# esp8285-programmer-v1_0.net
KiCad netlist of a schematic drawn in EAGLE
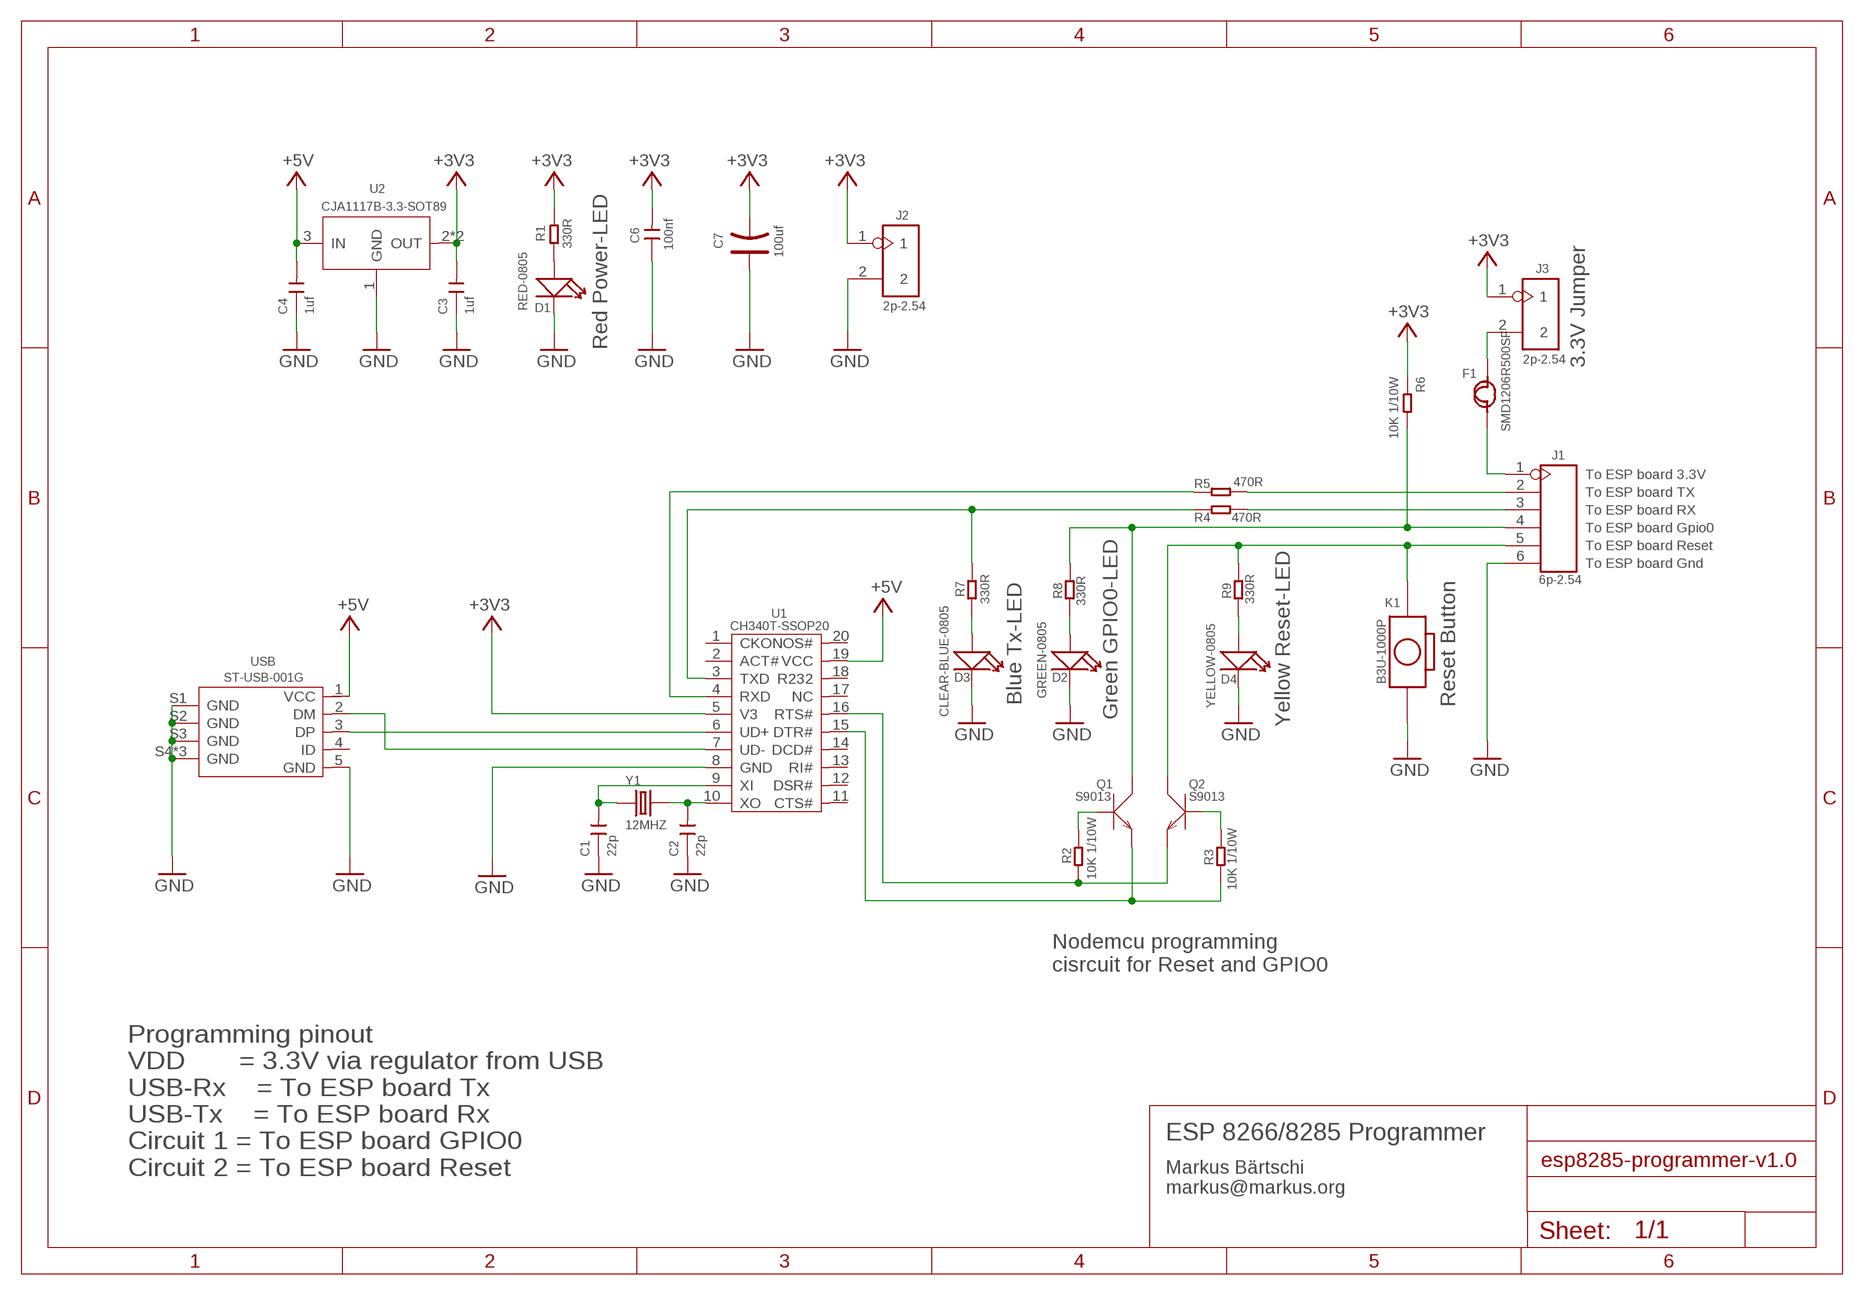
[diagram p0: schematic, sheet 1]

(export (version "E")
  (design (tool "Eeschema 10.0.6"))
  (components
    (comp (ref "C1")
      (value "22p")
      (footprint "eagle-import:C0603")
      (libsource (lib "eagle-import") (part "CERAMIC-10PF-50V-5%-NPO(0603)"))
    )
    (comp (ref "C2")
      (value "22p")
      (footprint "eagle-import:C0603")
      (libsource (lib "eagle-import") (part "CERAMIC-10PF-50V-5%-NPO(0603)"))
    )
    (comp (ref "C3")
      (value "1uf")
      (footprint "eagle-import:C0603")
      (fields (field (name "MPN") "CC0603KRX7R8BB105"))
      (libsource (lib "eagle-import") (part "CERAMIC-1UF-25V-10%-X7R(0603)"))
    )
    (comp (ref "C4")
      (value "1uf")
      (footprint "eagle-import:C0603")
      (fields (field (name "MPN") "CC0603KRX7R8BB105"))
      (libsource (lib "eagle-import") (part "CERAMIC-1UF-25V-10%-X7R(0603)"))
    )
    (comp (ref "C6")
      (value "100nf")
      (footprint "eagle-import:C0603")
      (fields (field (name "MPN") "CC0603KRX7R9BB104"))
      (libsource (lib "eagle-import") (part "CERAMIC-100NF-50V-10%-X7R(0603)"))
    )
    (comp (ref "C7")
      (value "100uf")
      (footprint "eagle-import:AVX-B")
      (fields (field (name "MPN") "TAJB107M006RNJ"))
      (libsource (lib "eagle-import") (part "TANTALUM-SMD-100UF-6.3V(AVX-B)"))
    )
    (comp (ref "D1")
      (value "RED-0805")
      (footprint "eagle-import:LED-0805")
      (fields (field (name "MPN") "17-215SURC/S530-A2/TR8"))
      (libsource (lib "eagle-import") (part "SMD-LED-CLEAR-RED(0805)"))
    )
    (comp (ref "D2")
      (value "GREEN-0805")
      (footprint "eagle-import:LED-0805")
      (fields (field (name "MPN") "17-215SYGC/S530-E2/TR8"))
      (libsource (lib "eagle-import") (part "SMD-LED-CLEAR-GREEN(0805)"))
    )
    (comp (ref "D3")
      (value "CLEAR-BLUE-0805")
      (footprint "eagle-import:LED-0805")
      (fields (field (name "MPN") "EL-17-215/BHC-AN1P2/3T"))
      (libsource (lib "eagle-import") (part "SMD-LED-CLEAR-BLUE(0805)"))
    )
    (comp (ref "D4")
      (value "YELLOW-0805")
      (footprint "eagle-import:LED-0805")
      (fields (field (name "MPN") "17-215UYC/S530-A3/TR8"))
      (libsource (lib "eagle-import") (part "SMD-LED-CLEAR-YELLOW(0805)"))
    )
    (comp (ref "F1")
      (value "SMD1206R500SF")
      (footprint "eagle-import:F1206")
      (libsource (lib "eagle-import") (part "SMD-PPTC-500MA(1206)"))
    )
    (comp (ref "J1")
      (value "6p-2.54")
      (footprint "eagle-import:H6-2.54")
      (fields (field (name "MPN") "P125-1106A1BS116A1"))
      (libsource (lib "eagle-import") (part "DIP-BLACK-MALE-HEADER(6P-2.54)"))
    )
    (comp (ref "J2")
      (value "2p-2.54")
      (footprint "eagle-import:H2-2.54")
      (fields (field (name "MPN") "P125-1102A0BS116A1"))
      (libsource (lib "eagle-import") (part "DIP-BLACK-MALE-HEADER-VERT(2P-2.54)"))
    )
    (comp (ref "J3")
      (value "2p-2.54")
      (footprint "eagle-import:H2-2.54")
      (fields (field (name "MPN") "P125-1102A0BS116A1"))
      (libsource (lib "eagle-import") (part "DIP-BLACK-MALE-HEADER-VERT(2P-2.54)"))
    )
    (comp (ref "K1")
      (value "B3U-1000P")
      (footprint "eagle-import:SW2-SMD-3.0X2.5X1.2+0.4MM")
      (libsource (lib "eagle-import") (part "SMD-BUTTON-WITHOUT-BOSS-(2P-3X2.5MM)"))
    )
    (comp (ref "Q1")
      (value "S9013")
      (footprint "eagle-import:SOT-23")
      (libsource (lib "eagle-import") (part "SMD-TRANSISTORS-NPN-25V-500MA-S9013(SOT-23)"))
    )
    (comp (ref "Q2")
      (value "S9013")
      (footprint "eagle-import:SOT-23")
      (libsource (lib "eagle-import") (part "SMD-TRANSISTORS-NPN-25V-500MA-S9013(SOT-23)"))
    )
    (comp (ref "R1")
      (value "330R")
      (footprint "eagle-import:R0603")
      (fields (field (name "MPN") "RC0603FR-07330RL"))
      (libsource (lib "eagle-import") (part "SMD-RES-330R-1%-1/10W(0603)"))
    )
    (comp (ref "R2")
      (value "10K 1/10W")
      (footprint "eagle-import:R0603")
      (fields (field (name "MPN") "RC0603JR-0710KL"))
      (libsource (lib "eagle-import") (part "SMD-RES-10K-5%-1/10W(0603)"))
    )
    (comp (ref "R3")
      (value "10K 1/10W")
      (footprint "eagle-import:R0603")
      (fields (field (name "MPN") "RC0603JR-0710KL"))
      (libsource (lib "eagle-import") (part "SMD-RES-10K-5%-1/10W(0603)"))
    )
    (comp (ref "R4")
      (value "470R")
      (footprint "eagle-import:R0603")
      (fields (field (name "MPN") "RC0603JR-07470RL"))
      (libsource (lib "eagle-import") (part "SMD-RES-470R-5%-1/10W(0603)"))
    )
    (comp (ref "R5")
      (value "470R")
      (footprint "eagle-import:R0603")
      (fields (field (name "MPN") "RC0603JR-07470RL"))
      (libsource (lib "eagle-import") (part "SMD-RES-470R-5%-1/10W(0603)"))
    )
    (comp (ref "R6")
      (value "10K 1/10W")
      (footprint "eagle-import:R0603")
      (fields (field (name "MPN") "RC0603JR-0710KL"))
      (libsource (lib "eagle-import") (part "SMD-RES-10K-5%-1/10W(0603)"))
    )
    (comp (ref "R7")
      (value "330R")
      (footprint "eagle-import:R0603")
      (fields (field (name "MPN") "RC0603FR-07330RL"))
      (libsource (lib "eagle-import") (part "SMD-RES-330R-1%-1/10W(0603)"))
    )
    (comp (ref "R8")
      (value "330R")
      (footprint "eagle-import:R0603")
      (fields (field (name "MPN") "RC0603FR-07330RL"))
      (libsource (lib "eagle-import") (part "SMD-RES-330R-1%-1/10W(0603)"))
    )
    (comp (ref "R9")
      (value "330R")
      (footprint "eagle-import:R0603")
      (fields (field (name "MPN") "RC0603FR-07330RL"))
      (libsource (lib "eagle-import") (part "SMD-RES-330R-1%-1/10W(0603)"))
    )
    (comp (ref "U1")
      (value "CH340T-SSOP20")
      (footprint "eagle-import:SSOP20-0.65-7.6X5.2MM")
      (fields (field (name "MPN") "CH340T"))
      (libsource (lib "eagle-import") (part "INTERFACE-CH340T(SSOP20)"))
    )
    (comp (ref "U2")
      (value "CJA1117B-3.3-SOT89")
      (footprint "eagle-import:SOT-89")
      (fields (field (name "MPN") "CJA1117B-3.3"))
      (libsource (lib "eagle-import") (part "PMIC-CJA1117B-3.3(SOT-89)"))
    )
    (comp (ref "USB")
      (value "ST-USB-001G")
      (footprint "eagle-import:MICRO-USB5+4P-SMD-0.65-B")
      (libsource (lib "eagle-import") (part "MICRO-USB-SMD-B-WITHOUT-POST-W/P(ST-USB-001G)"))
    )
    (comp (ref "Y1")
      (value "12MHZ")
      (footprint "eagle-import:X2-SMD-5.0X3.2X1.3MM")
      (fields (field (name "MPN") "5032/2P"))
      (libsource (lib "eagle-import") (part "SMD-CRYSTAL-12MHZ-20PF-20PPM-40R(2P-5.0X3.2MM)"))
    )
  )
  (nets
    (net (code "1") (name "+3V3") (class "Default")
      (node (ref "C3") (pin "2") (pinfunction "2_2") (pintype "passive"))
      (node (ref "C6") (pin "2") (pinfunction "2_2") (pintype "passive"))
      (node (ref "C7") (pin "-") (pinfunction "-_-") (pintype "passive"))
      (node (ref "J2") (pin "1") (pinfunction "1_1") (pintype "bidirectional"))
      (node (ref "J3") (pin "1") (pinfunction "1_1") (pintype "bidirectional"))
      (node (ref "R1") (pin "2") (pinfunction "2_2") (pintype "passive"))
      (node (ref "R6") (pin "1") (pinfunction "1_1") (pintype "passive"))
      (node (ref "U1") (pin "5") (pinfunction "V3_5") (pintype "power_in"))
      (node (ref "U2") (pin "2") (pinfunction "OUT_2") (pintype "bidirectional"))
      (node (ref "U2") (pin "4") (pinfunction "OUT_4") (pintype "bidirectional"))
    )
    (net (code "2") (name "+5V") (class "Default")
      (node (ref "C4") (pin "2") (pinfunction "2_2") (pintype "passive"))
      (node (ref "U1") (pin "19") (pinfunction "VCC_19") (pintype "power_in"))
      (node (ref "U2") (pin "3") (pinfunction "IN_3") (pintype "bidirectional"))
      (node (ref "USB") (pin "1") (pinfunction "VCC_1") (pintype "bidirectional"))
    )
    (net (code "3") (name "/NOS#") (class "Default")
      (node (ref "U1") (pin "20") (pinfunction "NOS#_20") (pintype "power_in"))
    )
    (net (code "4") (name "GND") (class "Default")
      (node (ref "C1") (pin "1") (pinfunction "1_1") (pintype "passive"))
      (node (ref "C2") (pin "1") (pinfunction "1_1") (pintype "passive"))
      (node (ref "C3") (pin "1") (pinfunction "1_1") (pintype "passive"))
      (node (ref "C4") (pin "1") (pinfunction "1_1") (pintype "passive"))
      (node (ref "C6") (pin "1") (pinfunction "1_1") (pintype "passive"))
      (node (ref "C7") (pin "+") (pinfunction "+_+") (pintype "passive"))
      (node (ref "D1") (pin "-") (pinfunction "-_-") (pintype "passive"))
      (node (ref "D2") (pin "-") (pinfunction "-_-") (pintype "passive"))
      (node (ref "D3") (pin "-") (pinfunction "-_-") (pintype "passive"))
      (node (ref "D4") (pin "-") (pinfunction "-_-") (pintype "passive"))
      (node (ref "J1") (pin "6") (pinfunction "6_6") (pintype "bidirectional"))
      (node (ref "J2") (pin "2") (pinfunction "2_2") (pintype "bidirectional"))
      (node (ref "K1") (pin "1") (pinfunction "1_1") (pintype "bidirectional"))
      (node (ref "U1") (pin "8") (pinfunction "GND_8") (pintype "power_in"))
      (node (ref "U2") (pin "1") (pinfunction "GND_1") (pintype "bidirectional"))
      (node (ref "USB") (pin "5") (pinfunction "GND_5") (pintype "bidirectional"))
      (node (ref "USB") (pin "S1") (pinfunction "GND_S1") (pintype "bidirectional"))
      (node (ref "USB") (pin "S2") (pinfunction "GND_S2") (pintype "bidirectional"))
      (node (ref "USB") (pin "S3") (pinfunction "GND_S3") (pintype "bidirectional"))
      (node (ref "USB") (pin "S4") (pinfunction "GND_S4") (pintype "bidirectional"))
      (node (ref "USB") (pin "S5") (pinfunction "GND_S5") (pintype "bidirectional"))
      (node (ref "USB") (pin "S6") (pinfunction "GND_S6") (pintype "bidirectional"))
    )
    (net (code "5") (name "Net-(D1-Pad+)") (class "Default")
      (node (ref "D1") (pin "+") (pinfunction "+_+") (pintype "passive"))
      (node (ref "R1") (pin "1") (pinfunction "1_1") (pintype "passive"))
    )
    (net (code "6") (name "Net-(D2-Pad+)") (class "Default")
      (node (ref "D2") (pin "+") (pinfunction "+_+") (pintype "passive"))
      (node (ref "R8") (pin "1") (pinfunction "1_1") (pintype "passive"))
    )
    (net (code "7") (name "Net-(D3-Pad+)") (class "Default")
      (node (ref "D3") (pin "+") (pinfunction "+_+") (pintype "passive"))
      (node (ref "R7") (pin "1") (pinfunction "1_1") (pintype "passive"))
    )
    (net (code "8") (name "Net-(D4-Pad+)") (class "Default")
      (node (ref "D4") (pin "+") (pinfunction "+_+") (pintype "passive"))
      (node (ref "R9") (pin "1") (pinfunction "1_1") (pintype "passive"))
    )
    (net (code "9") (name "Net-(F1-Pad1)") (class "Default")
      (node (ref "F1") (pin "1") (pinfunction "1_1") (pintype "bidirectional"))
      (node (ref "J1") (pin "1") (pinfunction "1_1") (pintype "bidirectional"))
    )
    (net (code "10") (name "Net-(F1-Pad2)") (class "Default")
      (node (ref "F1") (pin "2") (pinfunction "2_2") (pintype "bidirectional"))
      (node (ref "J3") (pin "2") (pinfunction "2_2") (pintype "bidirectional"))
    )
    (net (code "11") (name "Net-(J1-Pad2)") (class "Default")
      (node (ref "J1") (pin "2") (pinfunction "2_2") (pintype "bidirectional"))
      (node (ref "R5") (pin "2") (pinfunction "2_2") (pintype "passive"))
    )
    (net (code "12") (name "Net-(J1-Pad3)") (class "Default")
      (node (ref "J1") (pin "3") (pinfunction "3_3") (pintype "bidirectional"))
      (node (ref "R4") (pin "2") (pinfunction "2_2") (pintype "passive"))
    )
    (net (code "13") (name "Net-(Q1-B)") (class "Default")
      (node (ref "Q1") (pin "1") (pinfunction "B_1") (pintype "passive"))
      (node (ref "R2") (pin "1") (pinfunction "1_1") (pintype "passive"))
    )
    (net (code "14") (name "Net-(Q1-C)") (class "Default")
      (node (ref "J1") (pin "4") (pinfunction "4_4") (pintype "bidirectional"))
      (node (ref "Q1") (pin "3") (pinfunction "C_3") (pintype "passive"))
      (node (ref "R6") (pin "2") (pinfunction "2_2") (pintype "passive"))
      (node (ref "R8") (pin "2") (pinfunction "2_2") (pintype "passive"))
    )
    (net (code "15") (name "Net-(Q1-E)") (class "Default")
      (node (ref "Q1") (pin "2") (pinfunction "E_2") (pintype "passive"))
      (node (ref "R3") (pin "2") (pinfunction "2_2") (pintype "passive"))
      (node (ref "U1") (pin "15") (pinfunction "DTR#_15") (pintype "output"))
    )
    (net (code "16") (name "Net-(Q2-B)") (class "Default")
      (node (ref "Q2") (pin "1") (pinfunction "B_1") (pintype "passive"))
      (node (ref "R3") (pin "1") (pinfunction "1_1") (pintype "passive"))
    )
    (net (code "17") (name "Net-(Q2-C)") (class "Default")
      (node (ref "J1") (pin "5") (pinfunction "5_5") (pintype "bidirectional"))
      (node (ref "K1") (pin "2") (pinfunction "2_2") (pintype "bidirectional"))
      (node (ref "Q2") (pin "3") (pinfunction "C_3") (pintype "passive"))
      (node (ref "R9") (pin "2") (pinfunction "2_2") (pintype "passive"))
    )
    (net (code "18") (name "Net-(Q2-E)") (class "Default")
      (node (ref "Q2") (pin "2") (pinfunction "E_2") (pintype "passive"))
      (node (ref "R2") (pin "2") (pinfunction "2_2") (pintype "passive"))
      (node (ref "U1") (pin "16") (pinfunction "RTS#_16") (pintype "output"))
    )
    (net (code "19") (name "Net-(U1-RXD)") (class "Default")
      (node (ref "R5") (pin "1") (pinfunction "1_1") (pintype "passive"))
      (node (ref "U1") (pin "4") (pinfunction "RXD_4") (pintype "input"))
    )
    (net (code "20") (name "Net-(U1-TXD)") (class "Default")
      (node (ref "R4") (pin "1") (pinfunction "1_1") (pintype "passive"))
      (node (ref "R7") (pin "2") (pinfunction "2_2") (pintype "passive"))
      (node (ref "U1") (pin "3") (pinfunction "TXD_3") (pintype "output"))
    )
    (net (code "21") (name "Net-(U1-UD+)") (class "Default")
      (node (ref "U1") (pin "6") (pinfunction "UD+_6") (pintype "bidirectional"))
      (node (ref "USB") (pin "3") (pinfunction "DP_3") (pintype "bidirectional"))
    )
    (net (code "22") (name "Net-(U1-UD-)") (class "Default")
      (node (ref "U1") (pin "7") (pinfunction "UD-_7") (pintype "bidirectional"))
      (node (ref "USB") (pin "2") (pinfunction "DM_2") (pintype "bidirectional"))
    )
    (net (code "23") (name "Net-(U1-XI)") (class "Default")
      (node (ref "C1") (pin "2") (pinfunction "2_2") (pintype "passive"))
      (node (ref "U1") (pin "9") (pinfunction "XI_9") (pintype "input"))
      (node (ref "Y1") (pin "1") (pinfunction "1_1") (pintype "passive"))
    )
    (net (code "24") (name "Net-(U1-XO)") (class "Default")
      (node (ref "C2") (pin "2") (pinfunction "2_2") (pintype "passive"))
      (node (ref "U1") (pin "10") (pinfunction "XO_10") (pintype "output"))
      (node (ref "Y1") (pin "2") (pinfunction "2_2") (pintype "passive"))
    )
    (net (code "25") (name "unconnected-(U1-ACT#-Pad2)") (class "Default")
      (node (ref "U1") (pin "2") (pinfunction "ACT#_2") (pintype "output"))
    )
    (net (code "26") (name "unconnected-(U1-CKO-Pad1)") (class "Default")
      (node (ref "U1") (pin "1") (pinfunction "CKO_1") (pintype "output"))
    )
    (net (code "27") (name "unconnected-(U1-CTS#-Pad11)") (class "Default")
      (node (ref "U1") (pin "11") (pinfunction "CTS#_11") (pintype "input"))
    )
    (net (code "28") (name "unconnected-(U1-DCD#-Pad14)") (class "Default")
      (node (ref "U1") (pin "14") (pinfunction "DCD#_14") (pintype "input"))
    )
    (net (code "29") (name "unconnected-(U1-DSR#-Pad12)") (class "Default")
      (node (ref "U1") (pin "12") (pinfunction "DSR#_12") (pintype "input"))
    )
    (net (code "30") (name "unconnected-(U1-NC-Pad17)") (class "Default")
      (node (ref "U1") (pin "17") (pinfunction "NC_17") (pintype "no_connect"))
    )
    (net (code "31") (name "unconnected-(U1-R232-Pad18)") (class "Default")
      (node (ref "U1") (pin "18") (pinfunction "R232_18") (pintype "input"))
    )
    (net (code "32") (name "unconnected-(U1-RI#-Pad13)") (class "Default")
      (node (ref "U1") (pin "13") (pinfunction "RI#_13") (pintype "input"))
    )
    (net (code "33") (name "unconnected-(USB-ID-Pad4)") (class "Default")
      (node (ref "USB") (pin "4") (pinfunction "ID_4") (pintype "bidirectional"))
    )
  )
)
